# scheme.net
KiCad netlist of a schematic drawn in Altium Designer
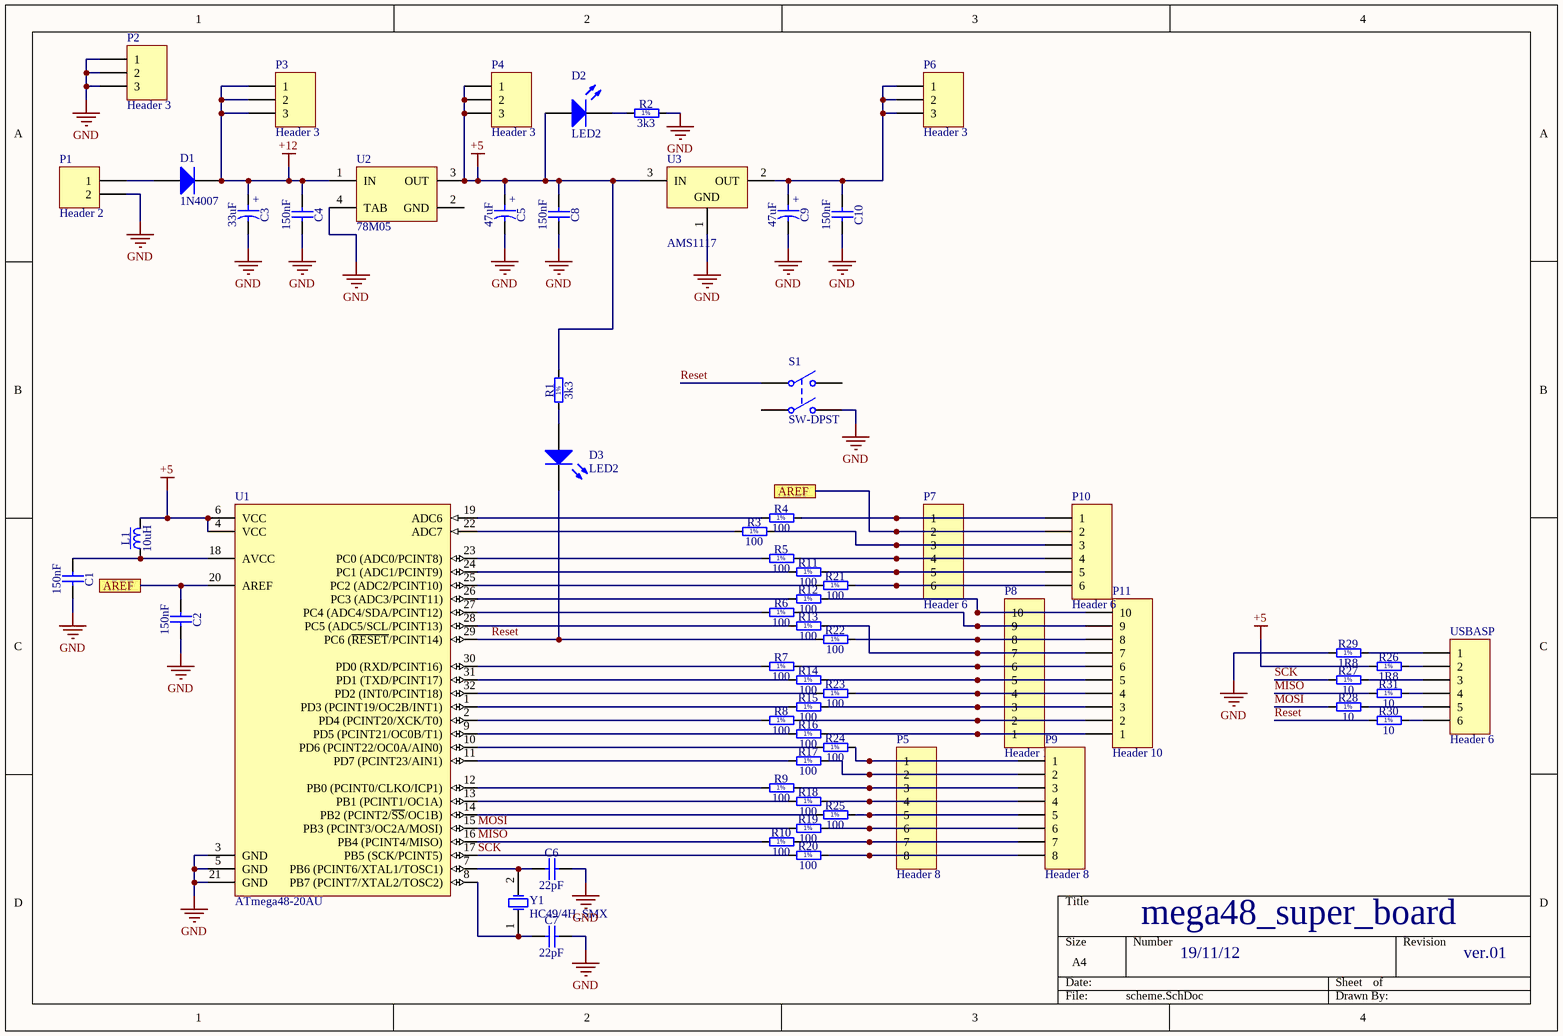
[diagram p0: scheme.SchDoc]

(export (version "E")
  (design (tool "Eeschema 10.0.6"))
  (components
    (comp (ref "C1")
      (value "150nF")
      (footprint "CAPC2013X100N")
      (description "Non-polarised capacitor")
      (fields
        (field (name "PART NUMBER") "CC0805_150NF_50V_10%_X5R")
        (field (name "VOLTAGE") "50V")
        (field (name "AUTHOR") "CERN DEM JLC")
      )
      (libsource (lib "Capacitors") (part "Capacitor - non polarized"))
    )
    (comp (ref "C2")
      (value "150nF")
      (footprint "CAPC2013X100N")
      (description "Non-polarised capacitor")
      (fields
        (field (name "PART NUMBER") "CC0805_150NF_50V_10%_X5R")
        (field (name "VOLTAGE") "50V")
        (field (name "AUTHOR") "CERN DEM JLC")
      )
      (libsource (lib "Capacitors") (part "Capacitor - non polarized"))
    )
    (comp (ref "C3")
      (value "33uF")
      (footprint "CAPMP7343X310N")
      (description "Polarised capacitor")
      (fields
        (field (name "PART NUMBER") "CTE7343-31_33UF_35V_10%_LESR0300")
        (field (name "VOLTAGE") "35V")
        (field (name "AUTHOR") "CERN DEM JLC")
      )
      (libsource (lib "Capacitors") (part "Capacitor - polarized"))
    )
    (comp (ref "C4")
      (value "150nF")
      (footprint "CAPC2013X100N")
      (description "Non-polarised capacitor")
      (fields
        (field (name "PART NUMBER") "CC0805_150NF_50V_10%_X5R")
        (field (name "VOLTAGE") "50V")
        (field (name "AUTHOR") "CERN DEM JLC")
      )
      (libsource (lib "Capacitors") (part "Capacitor - non polarized"))
    )
    (comp (ref "C5")
      (value "47uF")
      (footprint "CAPMP6032X280N")
      (description "Polarised capacitor")
      (fields
        (field (name "PART NUMBER") "CTE6032-28_47UF_10V_10%")
        (field (name "VOLTAGE") "10V")
        (field (name "AUTHOR") "CERN DEM JLC")
      )
      (libsource (lib "Capacitors") (part "Capacitor - polarized"))
    )
    (comp (ref "C6")
      (value "22pF")
      (footprint "CAPC1608X87N")
      (description "Non-polarised capacitor")
      (fields
        (field (name "PART NUMBER") "CC0603_22PF_50V_5%_NP0")
        (field (name "VOLTAGE") "50V")
        (field (name "AUTHOR") "CERN DEM JLC")
      )
      (libsource (lib "Capacitors") (part "Capacitor - non polarized"))
    )
    (comp (ref "C7")
      (value "22pF")
      (footprint "CAPC1608X87N")
      (description "Non-polarised capacitor")
      (fields
        (field (name "PART NUMBER") "CC0603_22PF_50V_5%_NP0")
        (field (name "VOLTAGE") "50V")
        (field (name "AUTHOR") "CERN DEM JLC")
      )
      (libsource (lib "Capacitors") (part "Capacitor - non polarized"))
    )
    (comp (ref "C8")
      (value "150nF")
      (footprint "CAPC2013X100N")
      (description "Non-polarised capacitor")
      (fields
        (field (name "PART NUMBER") "CC0805_150NF_50V_10%_X5R")
        (field (name "VOLTAGE") "50V")
        (field (name "AUTHOR") "CERN DEM JLC")
      )
      (libsource (lib "Capacitors") (part "Capacitor - non polarized"))
    )
    (comp (ref "C9")
      (value "47uF")
      (footprint "CAPMP6032X280N")
      (description "Polarised capacitor")
      (fields
        (field (name "PART NUMBER") "CTE6032-28_47UF_10V_10%")
        (field (name "VOLTAGE") "10V")
        (field (name "AUTHOR") "CERN DEM JLC")
      )
      (libsource (lib "Capacitors") (part "Capacitor - polarized"))
    )
    (comp (ref "C10")
      (value "150nF")
      (footprint "CAPC2013X100N")
      (description "Non-polarised capacitor")
      (fields
        (field (name "PART NUMBER") "CC0805_150NF_50V_10%_X5R")
        (field (name "VOLTAGE") "50V")
        (field (name "AUTHOR") "CERN DEM JLC")
      )
      (libsource (lib "Capacitors") (part "Capacitor - non polarized"))
    )
    (comp (ref "D1")
      (value "1N4007")
      (footprint "DO-41")
      (description "1.0 Ampere General Purpose Rectifier")
      (fields (field (name "PUBLISHER") "Altium Limited"))
      (libsource (lib "FSC Discrete Rectifier") (part "1N4007"))
    )
    (comp (ref "D2")
      (value "LED2")
      (footprint "6-0805_L")
      (description "Typical RED, GREEN, YELLOW, AMBER GaAs LED")
      (fields (field (name "PUBLISHER") "Altium Limited"))
      (libsource (lib "Miscellaneous Devices") (part "LED2"))
    )
    (comp (ref "D3")
      (value "LED2")
      (footprint "6-0805_L")
      (description "Typical RED, GREEN, YELLOW, AMBER GaAs LED")
      (fields (field (name "PUBLISHER") "Altium Limited"))
      (libsource (lib "Miscellaneous Devices") (part "LED2"))
    )
    (comp (ref "L1")
      (value "10uH")
      (footprint "INDC2012X105N")
      (description "Inductor With Core")
      (fields
        (field (name "PART NUMBER") "IND_10UH_10%_MURATA-PS_8200")
        (field (name "POWER") "500mA")
        (field (name "AUTHOR") "CERN DEM JLC")
      )
      (libsource (lib "Inductors & Transformers") (part "Inductor With Magnetic core"))
    )
    (comp (ref "P1")
      (value "Header 2")
      (footprint "HDR1X2")
      (description "Header, 2-Pin")
      (fields (field (name "PUBLISHER") "Altium Limited"))
      (libsource (lib "Miscellaneous Connectors") (part "Header 2"))
    )
    (comp (ref "P2")
      (value "Header 3")
      (footprint "HDR1X3")
      (description "Header, 3-Pin")
      (fields (field (name "PUBLISHER") "Altium Limited"))
      (libsource (lib "Miscellaneous Connectors") (part "Header 3"))
    )
    (comp (ref "P3")
      (value "Header 3")
      (footprint "HDR1X3")
      (description "Header, 3-Pin")
      (fields (field (name "PUBLISHER") "Altium Limited"))
      (libsource (lib "Miscellaneous Connectors") (part "Header 3"))
    )
    (comp (ref "P4")
      (value "Header 3")
      (footprint "HDR1X3")
      (description "Header, 3-Pin")
      (fields (field (name "PUBLISHER") "Altium Limited"))
      (libsource (lib "Miscellaneous Connectors") (part "Header 3"))
    )
    (comp (ref "P5")
      (value "Header 8")
      (footprint "HDR1X8")
      (description "Header, 8-Pin")
      (fields (field (name "PUBLISHER") "Altium Limited"))
      (libsource (lib "Miscellaneous Connectors") (part "Header 8"))
    )
    (comp (ref "P6")
      (value "Header 3")
      (footprint "HDR1X3")
      (description "Header, 3-Pin")
      (fields (field (name "PUBLISHER") "Altium Limited"))
      (libsource (lib "Miscellaneous Connectors") (part "Header 3"))
    )
    (comp (ref "P7")
      (value "Header 6")
      (footprint "HDR1X6")
      (description "Header, 6-Pin")
      (fields (field (name "PUBLISHER") "Altium Limited"))
      (libsource (lib "Miscellaneous Connectors") (part "Header 6"))
    )
    (comp (ref "P8")
      (value "Header 10")
      (footprint "HDR1X10")
      (description "Header, 10-Pin")
      (fields (field (name "PUBLISHER") "Altium Limited"))
      (libsource (lib "Miscellaneous Connectors") (part "Header 10"))
    )
    (comp (ref "P9")
      (value "Header 8")
      (footprint "HDR1X8")
      (description "Header, 8-Pin")
      (fields (field (name "PUBLISHER") "Altium Limited"))
      (libsource (lib "Miscellaneous Connectors") (part "Header 8"))
    )
    (comp (ref "P10")
      (value "Header 6")
      (footprint "HDR1X6")
      (description "Header, 6-Pin")
      (fields (field (name "PUBLISHER") "Altium Limited"))
      (libsource (lib "Miscellaneous Connectors") (part "Header 6"))
    )
    (comp (ref "P11")
      (value "Header 10")
      (footprint "HDR1X10")
      (description "Header, 10-Pin")
      (fields (field (name "PUBLISHER") "Altium Limited"))
      (libsource (lib "Miscellaneous Connectors") (part "Header 10"))
    )
    (comp (ref "R1")
      (value "3k3")
      (footprint "RESC2012X60N")
      (description "Resistor - 1%")
      (fields
        (field (name "PART NUMBER") "R0805_3K3_1%_0.125W_100PPM")
        (field (name "POWER") "0.125W")
        (field (name "AUTHOR") "CERN DEM JLC")
      )
      (libsource (lib "Resistors") (part "Resistor - 1%"))
    )
    (comp (ref "R2")
      (value "3k3")
      (footprint "RESC2012X60N")
      (description "Resistor - 1%")
      (fields
        (field (name "PART NUMBER") "R0805_3K3_1%_0.125W_100PPM")
        (field (name "POWER") "0.125W")
        (field (name "AUTHOR") "CERN DEM JLC")
      )
      (libsource (lib "Resistors") (part "Resistor - 1%"))
    )
    (comp (ref "R3")
      (value "100")
      (footprint "RESC1608X55N")
      (description "Resistor - 1%")
      (fields
        (field (name "PART NUMBER") "R0603_100R_1%_0.1W_100PPM")
        (field (name "POWER") "0.1W")
        (field (name "AUTHOR") "CERN DEM JLC")
      )
      (libsource (lib "Resistors") (part "Resistor - 1%"))
    )
    (comp (ref "R4")
      (value "100")
      (footprint "RESC1608X55N")
      (description "Resistor - 1%")
      (fields
        (field (name "PART NUMBER") "R0603_100R_1%_0.1W_100PPM")
        (field (name "POWER") "0.1W")
        (field (name "AUTHOR") "CERN DEM JLC")
      )
      (libsource (lib "Resistors") (part "Resistor - 1%"))
    )
    (comp (ref "R5")
      (value "100")
      (footprint "RESC1608X55N")
      (description "Resistor - 1%")
      (fields
        (field (name "PART NUMBER") "R0603_100R_1%_0.1W_100PPM")
        (field (name "POWER") "0.1W")
        (field (name "AUTHOR") "CERN DEM JLC")
      )
      (libsource (lib "Resistors") (part "Resistor - 1%"))
    )
    (comp (ref "R6")
      (value "100")
      (footprint "RESC1608X55N")
      (description "Resistor - 1%")
      (fields
        (field (name "PART NUMBER") "R0603_100R_1%_0.1W_100PPM")
        (field (name "POWER") "0.1W")
        (field (name "AUTHOR") "CERN DEM JLC")
      )
      (libsource (lib "Resistors") (part "Resistor - 1%"))
    )
    (comp (ref "R7")
      (value "100")
      (footprint "RESC1608X55N")
      (description "Resistor - 1%")
      (fields
        (field (name "PART NUMBER") "R0603_100R_1%_0.1W_100PPM")
        (field (name "POWER") "0.1W")
        (field (name "AUTHOR") "CERN DEM JLC")
      )
      (libsource (lib "Resistors") (part "Resistor - 1%"))
    )
    (comp (ref "R8")
      (value "100")
      (footprint "RESC1608X55N")
      (description "Resistor - 1%")
      (fields
        (field (name "PART NUMBER") "R0603_100R_1%_0.1W_100PPM")
        (field (name "POWER") "0.1W")
        (field (name "AUTHOR") "CERN DEM JLC")
      )
      (libsource (lib "Resistors") (part "Resistor - 1%"))
    )
    (comp (ref "R9")
      (value "100")
      (footprint "RESC1608X55N")
      (description "Resistor - 1%")
      (fields
        (field (name "PART NUMBER") "R0603_100R_1%_0.1W_100PPM")
        (field (name "POWER") "0.1W")
        (field (name "AUTHOR") "CERN DEM JLC")
      )
      (libsource (lib "Resistors") (part "Resistor - 1%"))
    )
    (comp (ref "R10")
      (value "100")
      (footprint "RESC1608X55N")
      (description "Resistor - 1%")
      (fields
        (field (name "PART NUMBER") "R0603_100R_1%_0.1W_100PPM")
        (field (name "POWER") "0.1W")
        (field (name "AUTHOR") "CERN DEM JLC")
      )
      (libsource (lib "Resistors") (part "Resistor - 1%"))
    )
    (comp (ref "R11")
      (value "100")
      (footprint "RESC1608X55N")
      (description "Resistor - 1%")
      (fields
        (field (name "PART NUMBER") "R0603_100R_1%_0.1W_100PPM")
        (field (name "POWER") "0.1W")
        (field (name "AUTHOR") "CERN DEM JLC")
      )
      (libsource (lib "Resistors") (part "Resistor - 1%"))
    )
    (comp (ref "R12")
      (value "100")
      (footprint "RESC1608X55N")
      (description "Resistor - 1%")
      (fields
        (field (name "PART NUMBER") "R0603_100R_1%_0.1W_100PPM")
        (field (name "POWER") "0.1W")
        (field (name "AUTHOR") "CERN DEM JLC")
      )
      (libsource (lib "Resistors") (part "Resistor - 1%"))
    )
    (comp (ref "R13")
      (value "100")
      (footprint "RESC1608X55N")
      (description "Resistor - 1%")
      (fields
        (field (name "PART NUMBER") "R0603_100R_1%_0.1W_100PPM")
        (field (name "POWER") "0.1W")
        (field (name "AUTHOR") "CERN DEM JLC")
      )
      (libsource (lib "Resistors") (part "Resistor - 1%"))
    )
    (comp (ref "R14")
      (value "100")
      (footprint "RESC1608X55N")
      (description "Resistor - 1%")
      (fields
        (field (name "PART NUMBER") "R0603_100R_1%_0.1W_100PPM")
        (field (name "POWER") "0.1W")
        (field (name "AUTHOR") "CERN DEM JLC")
      )
      (libsource (lib "Resistors") (part "Resistor - 1%"))
    )
    (comp (ref "R15")
      (value "100")
      (footprint "RESC1608X55N")
      (description "Resistor - 1%")
      (fields
        (field (name "PART NUMBER") "R0603_100R_1%_0.1W_100PPM")
        (field (name "POWER") "0.1W")
        (field (name "AUTHOR") "CERN DEM JLC")
      )
      (libsource (lib "Resistors") (part "Resistor - 1%"))
    )
    (comp (ref "R16")
      (value "100")
      (footprint "RESC1608X55N")
      (description "Resistor - 1%")
      (fields
        (field (name "PART NUMBER") "R0603_100R_1%_0.1W_100PPM")
        (field (name "POWER") "0.1W")
        (field (name "AUTHOR") "CERN DEM JLC")
      )
      (libsource (lib "Resistors") (part "Resistor - 1%"))
    )
    (comp (ref "R17")
      (value "100")
      (footprint "RESC1608X55N")
      (description "Resistor - 1%")
      (fields
        (field (name "PART NUMBER") "R0603_100R_1%_0.1W_100PPM")
        (field (name "POWER") "0.1W")
        (field (name "AUTHOR") "CERN DEM JLC")
      )
      (libsource (lib "Resistors") (part "Resistor - 1%"))
    )
    (comp (ref "R18")
      (value "100")
      (footprint "RESC1608X55N")
      (description "Resistor - 1%")
      (fields
        (field (name "PART NUMBER") "R0603_100R_1%_0.1W_100PPM")
        (field (name "POWER") "0.1W")
        (field (name "AUTHOR") "CERN DEM JLC")
      )
      (libsource (lib "Resistors") (part "Resistor - 1%"))
    )
    (comp (ref "R19")
      (value "100")
      (footprint "RESC1608X55N")
      (description "Resistor - 1%")
      (fields
        (field (name "PART NUMBER") "R0603_100R_1%_0.1W_100PPM")
        (field (name "POWER") "0.1W")
        (field (name "AUTHOR") "CERN DEM JLC")
      )
      (libsource (lib "Resistors") (part "Resistor - 1%"))
    )
    (comp (ref "R20")
      (value "100")
      (footprint "RESC1608X55N")
      (description "Resistor - 1%")
      (fields
        (field (name "PART NUMBER") "R0603_100R_1%_0.1W_100PPM")
        (field (name "POWER") "0.1W")
        (field (name "AUTHOR") "CERN DEM JLC")
      )
      (libsource (lib "Resistors") (part "Resistor - 1%"))
    )
    (comp (ref "R21")
      (value "100")
      (footprint "RESC1608X55N")
      (description "Resistor - 1%")
      (fields
        (field (name "PART NUMBER") "R0603_100R_1%_0.1W_100PPM")
        (field (name "POWER") "0.1W")
        (field (name "AUTHOR") "CERN DEM JLC")
      )
      (libsource (lib "Resistors") (part "Resistor - 1%"))
    )
    (comp (ref "R22")
      (value "100")
      (footprint "RESC1608X55N")
      (description "Resistor - 1%")
      (fields
        (field (name "PART NUMBER") "R0603_100R_1%_0.1W_100PPM")
        (field (name "POWER") "0.1W")
        (field (name "AUTHOR") "CERN DEM JLC")
      )
      (libsource (lib "Resistors") (part "Resistor - 1%"))
    )
    (comp (ref "R23")
      (value "100")
      (footprint "RESC1608X55N")
      (description "Resistor - 1%")
      (fields
        (field (name "PART NUMBER") "R0603_100R_1%_0.1W_100PPM")
        (field (name "POWER") "0.1W")
        (field (name "AUTHOR") "CERN DEM JLC")
      )
      (libsource (lib "Resistors") (part "Resistor - 1%"))
    )
    (comp (ref "R24")
      (value "100")
      (footprint "RESC1608X55N")
      (description "Resistor - 1%")
      (fields
        (field (name "PART NUMBER") "R0603_100R_1%_0.1W_100PPM")
        (field (name "POWER") "0.1W")
        (field (name "AUTHOR") "CERN DEM JLC")
      )
      (libsource (lib "Resistors") (part "Resistor - 1%"))
    )
    (comp (ref "R25")
      (value "100")
      (footprint "RESC1608X55N")
      (description "Resistor - 1%")
      (fields
        (field (name "PART NUMBER") "R0603_100R_1%_0.1W_100PPM")
        (field (name "POWER") "0.1W")
        (field (name "AUTHOR") "CERN DEM JLC")
      )
      (libsource (lib "Resistors") (part "Resistor - 1%"))
    )
    (comp (ref "R26")
      (value "1R8")
      (footprint "RESC1608X55N")
      (description "Resistor - 1%")
      (fields
        (field (name "PART NUMBER") "R0603_1R8_1%_0.1W_200PPM")
        (field (name "POWER") "0.1W")
        (field (name "AUTHOR") "CERN DEM JLC")
      )
      (libsource (lib "Resistors") (part "Resistor - 1%"))
    )
    (comp (ref "R27")
      (value "10")
      (footprint "RESC1608X55N")
      (description "Resistor - 1%")
      (fields
        (field (name "PART NUMBER") "R0603_10R_1%_0.1W_200PPM")
        (field (name "POWER") "0.1W")
        (field (name "AUTHOR") "CERN DEM JLC")
      )
      (libsource (lib "Resistors") (part "Resistor - 1%"))
    )
    (comp (ref "R28")
      (value "10")
      (footprint "RESC1608X55N")
      (description "Resistor - 1%")
      (fields
        (field (name "PART NUMBER") "R0603_10R_1%_0.1W_200PPM")
        (field (name "POWER") "0.1W")
        (field (name "AUTHOR") "CERN DEM JLC")
      )
      (libsource (lib "Resistors") (part "Resistor - 1%"))
    )
    (comp (ref "R29")
      (value "1R8")
      (footprint "RESC1608X55N")
      (description "Resistor - 1%")
      (fields
        (field (name "PART NUMBER") "R0603_1R8_1%_0.1W_200PPM")
        (field (name "POWER") "0.1W")
        (field (name "AUTHOR") "CERN DEM JLC")
      )
      (libsource (lib "Resistors") (part "Resistor - 1%"))
    )
    (comp (ref "R30")
      (value "10")
      (footprint "RESC1608X55N")
      (description "Resistor - 1%")
      (fields
        (field (name "PART NUMBER") "R0603_10R_1%_0.1W_200PPM")
        (field (name "POWER") "0.1W")
        (field (name "AUTHOR") "CERN DEM JLC")
      )
      (libsource (lib "Resistors") (part "Resistor - 1%"))
    )
    (comp (ref "R31")
      (value "10")
      (footprint "RESC1608X55N")
      (description "Resistor - 1%")
      (fields
        (field (name "PART NUMBER") "R0603_10R_1%_0.1W_200PPM")
        (field (name "POWER") "0.1W")
        (field (name "AUTHOR") "CERN DEM JLC")
      )
      (libsource (lib "Resistors") (part "Resistor - 1%"))
    )
    (comp (ref "S1")
      (value "SW-DPST")
      (footprint "DPST-4")
      (description "Double-Pole, Single-Throw Switch")
      (fields (field (name "PUBLISHER") "Altium Limited"))
      (libsource (lib "Miscellaneous Devices") (part "SW-DPST"))
    )
    (comp (ref "U1")
      (value "ATmega48-20AU")
      (footprint "32A_N")
      (libsource (lib "Atmel Microcontroller megaAVR") (part "ATmega48-20AU"))
    )
    (comp (ref "U2")
      (value "78M05")
      (footprint "TS3B_N")
      (description "Series 3-Terminal Positive Regulators, 3-pin TO-263")
      (fields (field (name "PARTNUMBER") "LM340S-5.0") (field (name "MANUFACTURER") "National Semiconductor"))
      (libsource (lib "National Semiconductor LDO") (part "LM340S-5.0"))
    )
    (comp (ref "U3")
      (value "AMS1117")
      (footprint "ADI-KC-3_N")
      (fields (field (name "MANUFACTURER") "Analog Devices") (field (name "PARTNUMBER") "ADP3338AKCZ-3.3-RL"))
      (libsource (lib "Analog Devices Power Management Linear Regulators") (part "ADP3338AKCZ-3.3-RL"))
    )
    (comp (ref "USBASP")
      (value "Header 6")
      (footprint "HDR1X6")
      (description "Header, 6-Pin")
      (fields (field (name "PUBLISHER") "Altium Limited"))
      (libsource (lib "Miscellaneous Connectors") (part "Header 6"))
    )
    (comp (ref "Y1")
      (value "HC49/4H_SMX")
      (footprint "HC49/4H_SMX")
      (description "Surface Mount Quartz Crystal")
      (fields (field (name "PUBLISHER") "Altium Limited"))
      (libsource (lib "C-MAC Crystal Oscillator") (part "HC49/4H_SMX"))
    )
  )
  (nets
    (net (code "1") (name "+5") (class "Default")
      (node (ref "C5") (pin "1") (pinfunction "1_1") (pintype "passive"))
      (node (ref "C8") (pin "1") (pinfunction "1_1") (pintype "passive"))
      (node (ref "D2") (pin "1") (pinfunction "A_1") (pintype "passive"))
      (node (ref "L1") (pin "2") (pinfunction "2_2") (pintype "passive"))
      (node (ref "P4") (pin "1") (pinfunction "1_1") (pintype "passive"))
      (node (ref "P4") (pin "2") (pinfunction "2_2") (pintype "passive"))
      (node (ref "P4") (pin "3") (pinfunction "3_3") (pintype "passive"))
      (node (ref "R1") (pin "2") (pinfunction "2_2") (pintype "passive"))
      (node (ref "R26") (pin "1") (pinfunction "1_1") (pintype "passive"))
      (node (ref "U1") (pin "4") (pinfunction "VCC_4") (pintype "power_in"))
      (node (ref "U1") (pin "6") (pinfunction "VCC_6") (pintype "power_in"))
      (node (ref "U2") (pin "3") (pinfunction "OUT_3") (pintype "power_in"))
      (node (ref "U3") (pin "3") (pinfunction "IN_3") (pintype "power_in"))
    )
    (net (code "2") (name "+12") (class "Default")
      (node (ref "C3") (pin "1") (pinfunction "1_1") (pintype "passive"))
      (node (ref "C4") (pin "1") (pinfunction "1_1") (pintype "passive"))
      (node (ref "D1") (pin "2") (pinfunction "K_2") (pintype "passive"))
      (node (ref "P3") (pin "1") (pinfunction "1_1") (pintype "passive"))
      (node (ref "P3") (pin "2") (pinfunction "2_2") (pintype "passive"))
      (node (ref "P3") (pin "3") (pinfunction "3_3") (pintype "passive"))
      (node (ref "U2") (pin "1") (pinfunction "IN_1") (pintype "power_in"))
    )
    (net (code "3") (name "/AREF") (class "Default")
      (node (ref "C2") (pin "1") (pinfunction "1_1") (pintype "passive"))
      (node (ref "P10") (pin "2") (pinfunction "2_2") (pintype "passive"))
      (node (ref "P7") (pin "2") (pinfunction "2_2") (pintype "passive"))
      (node (ref "U1") (pin "20") (pinfunction "AREF_20") (pintype "passive"))
    )
    (net (code "4") (name "/MISO") (class "Default")
      (node (ref "R10") (pin "1") (pinfunction "1_1") (pintype "passive"))
      (node (ref "R31") (pin "1") (pinfunction "1_1") (pintype "passive"))
      (node (ref "U1") (pin "16") (pinfunction "PB4_(PCINT4/MISO)_16") (pintype "bidirectional"))
    )
    (net (code "5") (name "/MOSI") (class "Default")
      (node (ref "R19") (pin "1") (pinfunction "1_1") (pintype "passive"))
      (node (ref "R28") (pin "1") (pinfunction "1_1") (pintype "passive"))
      (node (ref "U1") (pin "15") (pinfunction "PB3_(PCINT3/OC2A/MOSI)_15") (pintype "bidirectional"))
    )
    (net (code "6") (name "/Reset") (class "Default")
      (node (ref "D3") (pin "2") (pinfunction "K_2") (pintype "passive"))
      (node (ref "R22") (pin "1") (pinfunction "1_1") (pintype "passive"))
      (node (ref "R30") (pin "1") (pinfunction "1_1") (pintype "passive"))
      (node (ref "S1") (pin "1") (pinfunction "COMMON1_1") (pintype "passive"))
      (node (ref "U1") (pin "29") (pinfunction "PC6_(~{RESET}/PCINT14)_29") (pintype "bidirectional"))
    )
    (net (code "7") (name "/SCK") (class "Default")
      (node (ref "R20") (pin "1") (pinfunction "1_1") (pintype "passive"))
      (node (ref "R27") (pin "1") (pinfunction "1_1") (pintype "passive"))
      (node (ref "U1") (pin "17") (pinfunction "PB5_(SCK/PCINT5)_17") (pintype "bidirectional"))
    )
    (net (code "8") (name "GND") (class "Default")
      (node (ref "C1") (pin "2") (pinfunction "2_2") (pintype "passive"))
      (node (ref "C10") (pin "2") (pinfunction "2_2") (pintype "passive"))
      (node (ref "C2") (pin "2") (pinfunction "2_2") (pintype "passive"))
      (node (ref "C3") (pin "2") (pinfunction "2_2") (pintype "passive"))
      (node (ref "C4") (pin "2") (pinfunction "2_2") (pintype "passive"))
      (node (ref "C5") (pin "2") (pinfunction "2_2") (pintype "passive"))
      (node (ref "C6") (pin "2") (pinfunction "2_2") (pintype "passive"))
      (node (ref "C7") (pin "2") (pinfunction "2_2") (pintype "passive"))
      (node (ref "C8") (pin "2") (pinfunction "2_2") (pintype "passive"))
      (node (ref "C9") (pin "2") (pinfunction "2_2") (pintype "passive"))
      (node (ref "P1") (pin "2") (pinfunction "2_2") (pintype "passive"))
      (node (ref "P2") (pin "1") (pinfunction "1_1") (pintype "passive"))
      (node (ref "P2") (pin "2") (pinfunction "2_2") (pintype "passive"))
      (node (ref "P2") (pin "3") (pinfunction "3_3") (pintype "passive"))
      (node (ref "R2") (pin "2") (pinfunction "2_2") (pintype "passive"))
      (node (ref "R29") (pin "1") (pinfunction "1_1") (pintype "passive"))
      (node (ref "S1") (pin "4") (pinfunction "NO2_4") (pintype "passive"))
      (node (ref "U1") (pin "21") (pinfunction "GND_21") (pintype "power_in"))
      (node (ref "U1") (pin "3") (pinfunction "GND_3") (pintype "power_in"))
      (node (ref "U1") (pin "5") (pinfunction "GND_5") (pintype "power_in"))
      (node (ref "U2") (pin "4") (pinfunction "TAB_4") (pintype "power_in"))
      (node (ref "U3") (pin "1") (pinfunction "GND_1") (pintype "power_in"))
    )
    (net (code "9") (name "Net-(D1-A)") (class "Default")
      (node (ref "D1") (pin "1") (pinfunction "A_1") (pintype "passive"))
      (node (ref "P1") (pin "1") (pinfunction "1_1") (pintype "passive"))
    )
    (net (code "10") (name "Net-(D2-K)") (class "Default")
      (node (ref "D2") (pin "2") (pinfunction "K_2") (pintype "passive"))
      (node (ref "R2") (pin "1") (pinfunction "1_1") (pintype "passive"))
    )
    (net (code "11") (name "Net-(D3-A)") (class "Default")
      (node (ref "D3") (pin "1") (pinfunction "A_1") (pintype "passive"))
      (node (ref "R1") (pin "1") (pinfunction "1_1") (pintype "passive"))
    )
    (net (code "12") (name "Net-(P5-Pad1)") (class "Default")
      (node (ref "P5") (pin "1") (pinfunction "1_1") (pintype "passive"))
      (node (ref "P9") (pin "1") (pinfunction "1_1") (pintype "passive"))
      (node (ref "R24") (pin "2") (pinfunction "2_2") (pintype "passive"))
    )
    (net (code "13") (name "Net-(P5-Pad2)") (class "Default")
      (node (ref "P5") (pin "2") (pinfunction "2_2") (pintype "passive"))
      (node (ref "P9") (pin "2") (pinfunction "2_2") (pintype "passive"))
      (node (ref "R17") (pin "2") (pinfunction "2_2") (pintype "passive"))
    )
    (net (code "14") (name "Net-(P5-Pad3)") (class "Default")
      (node (ref "P5") (pin "3") (pinfunction "3_3") (pintype "passive"))
      (node (ref "P9") (pin "3") (pinfunction "3_3") (pintype "passive"))
      (node (ref "R9") (pin "2") (pinfunction "2_2") (pintype "passive"))
    )
    (net (code "15") (name "Net-(P5-Pad4)") (class "Default")
      (node (ref "P5") (pin "4") (pinfunction "4_4") (pintype "passive"))
      (node (ref "P9") (pin "4") (pinfunction "4_4") (pintype "passive"))
      (node (ref "R18") (pin "2") (pinfunction "2_2") (pintype "passive"))
    )
    (net (code "16") (name "Net-(P5-Pad5)") (class "Default")
      (node (ref "P5") (pin "5") (pinfunction "5_5") (pintype "passive"))
      (node (ref "P9") (pin "5") (pinfunction "5_5") (pintype "passive"))
      (node (ref "R25") (pin "2") (pinfunction "2_2") (pintype "passive"))
    )
    (net (code "17") (name "Net-(P5-Pad6)") (class "Default")
      (node (ref "P5") (pin "6") (pinfunction "6_6") (pintype "passive"))
      (node (ref "P9") (pin "6") (pinfunction "6_6") (pintype "passive"))
      (node (ref "R19") (pin "2") (pinfunction "2_2") (pintype "passive"))
    )
    (net (code "18") (name "Net-(P5-Pad7)") (class "Default")
      (node (ref "P5") (pin "7") (pinfunction "7_7") (pintype "passive"))
      (node (ref "P9") (pin "7") (pinfunction "7_7") (pintype "passive"))
      (node (ref "R10") (pin "2") (pinfunction "2_2") (pintype "passive"))
    )
    (net (code "19") (name "Net-(P5-Pad8)") (class "Default")
      (node (ref "P5") (pin "8") (pinfunction "8_8") (pintype "passive"))
      (node (ref "P9") (pin "8") (pinfunction "8_8") (pintype "passive"))
      (node (ref "R20") (pin "2") (pinfunction "2_2") (pintype "passive"))
    )
    (net (code "20") (name "Net-(P10-Pad1)") (class "Default")
      (node (ref "P10") (pin "1") (pinfunction "1_1") (pintype "passive"))
      (node (ref "P7") (pin "1") (pinfunction "1_1") (pintype "passive"))
      (node (ref "R4") (pin "2") (pinfunction "2_2") (pintype "passive"))
    )
    (net (code "21") (name "Net-(P10-Pad3)") (class "Default")
      (node (ref "P10") (pin "3") (pinfunction "3_3") (pintype "passive"))
      (node (ref "P7") (pin "3") (pinfunction "3_3") (pintype "passive"))
      (node (ref "R3") (pin "2") (pinfunction "2_2") (pintype "passive"))
    )
    (net (code "22") (name "Net-(P10-Pad4)") (class "Default")
      (node (ref "P10") (pin "4") (pinfunction "4_4") (pintype "passive"))
      (node (ref "P7") (pin "4") (pinfunction "4_4") (pintype "passive"))
      (node (ref "R5") (pin "2") (pinfunction "2_2") (pintype "passive"))
    )
    (net (code "23") (name "Net-(P10-Pad5)") (class "Default")
      (node (ref "P10") (pin "5") (pinfunction "5_5") (pintype "passive"))
      (node (ref "P7") (pin "5") (pinfunction "5_5") (pintype "passive"))
      (node (ref "R11") (pin "2") (pinfunction "2_2") (pintype "passive"))
    )
    (net (code "24") (name "Net-(P10-Pad6)") (class "Default")
      (node (ref "P10") (pin "6") (pinfunction "6_6") (pintype "passive"))
      (node (ref "P7") (pin "6") (pinfunction "6_6") (pintype "passive"))
      (node (ref "R21") (pin "2") (pinfunction "2_2") (pintype "passive"))
    )
    (net (code "25") (name "Net-(P11-Pad1)") (class "Default")
      (node (ref "P11") (pin "1") (pinfunction "1_1") (pintype "passive"))
      (node (ref "P8") (pin "1") (pinfunction "1_1") (pintype "passive"))
      (node (ref "R16") (pin "2") (pinfunction "2_2") (pintype "passive"))
    )
    (net (code "26") (name "Net-(P11-Pad2)") (class "Default")
      (node (ref "P11") (pin "2") (pinfunction "2_2") (pintype "passive"))
      (node (ref "P8") (pin "2") (pinfunction "2_2") (pintype "passive"))
      (node (ref "R8") (pin "2") (pinfunction "2_2") (pintype "passive"))
    )
    (net (code "27") (name "Net-(P11-Pad3)") (class "Default")
      (node (ref "P11") (pin "3") (pinfunction "3_3") (pintype "passive"))
      (node (ref "P8") (pin "3") (pinfunction "3_3") (pintype "passive"))
      (node (ref "R15") (pin "2") (pinfunction "2_2") (pintype "passive"))
    )
    (net (code "28") (name "Net-(P11-Pad4)") (class "Default")
      (node (ref "P11") (pin "4") (pinfunction "4_4") (pintype "passive"))
      (node (ref "P8") (pin "4") (pinfunction "4_4") (pintype "passive"))
      (node (ref "R23") (pin "2") (pinfunction "2_2") (pintype "passive"))
    )
    (net (code "29") (name "Net-(P11-Pad5)") (class "Default")
      (node (ref "P11") (pin "5") (pinfunction "5_5") (pintype "passive"))
      (node (ref "P8") (pin "5") (pinfunction "5_5") (pintype "passive"))
      (node (ref "R14") (pin "2") (pinfunction "2_2") (pintype "passive"))
    )
    (net (code "30") (name "Net-(P11-Pad6)") (class "Default")
      (node (ref "P11") (pin "6") (pinfunction "6_6") (pintype "passive"))
      (node (ref "P8") (pin "6") (pinfunction "6_6") (pintype "passive"))
      (node (ref "R7") (pin "2") (pinfunction "2_2") (pintype "passive"))
    )
    (net (code "31") (name "Net-(P11-Pad7)") (class "Default")
      (node (ref "P11") (pin "7") (pinfunction "7_7") (pintype "passive"))
      (node (ref "P8") (pin "7") (pinfunction "7_7") (pintype "passive"))
      (node (ref "R13") (pin "2") (pinfunction "2_2") (pintype "passive"))
    )
    (net (code "32") (name "Net-(P11-Pad8)") (class "Default")
      (node (ref "P11") (pin "8") (pinfunction "8_8") (pintype "passive"))
      (node (ref "P8") (pin "8") (pinfunction "8_8") (pintype "passive"))
      (node (ref "R22") (pin "2") (pinfunction "2_2") (pintype "passive"))
    )
    (net (code "33") (name "Net-(P11-Pad9)") (class "Default")
      (node (ref "P11") (pin "9") (pinfunction "9_9") (pintype "passive"))
      (node (ref "P8") (pin "9") (pinfunction "9_9") (pintype "passive"))
      (node (ref "R6") (pin "2") (pinfunction "2_2") (pintype "passive"))
    )
    (net (code "34") (name "Net-(P11-Pad10)") (class "Default")
      (node (ref "P11") (pin "10") (pinfunction "10_10") (pintype "passive"))
      (node (ref "P8") (pin "10") (pinfunction "10_10") (pintype "passive"))
      (node (ref "R12") (pin "2") (pinfunction "2_2") (pintype "passive"))
    )
    (net (code "35") (name "Net-(R26-Pad2)") (class "Default")
      (node (ref "R26") (pin "2") (pinfunction "2_2") (pintype "passive"))
      (node (ref "USBASP") (pin "2") (pinfunction "2_2") (pintype "passive"))
    )
    (net (code "36") (name "Net-(R27-Pad2)") (class "Default")
      (node (ref "R27") (pin "2") (pinfunction "2_2") (pintype "passive"))
      (node (ref "USBASP") (pin "3") (pinfunction "3_3") (pintype "passive"))
    )
    (net (code "37") (name "Net-(R28-Pad2)") (class "Default")
      (node (ref "R28") (pin "2") (pinfunction "2_2") (pintype "passive"))
      (node (ref "USBASP") (pin "5") (pinfunction "5_5") (pintype "passive"))
    )
    (net (code "38") (name "Net-(R29-Pad2)") (class "Default")
      (node (ref "R29") (pin "2") (pinfunction "2_2") (pintype "passive"))
      (node (ref "USBASP") (pin "1") (pinfunction "1_1") (pintype "passive"))
    )
    (net (code "39") (name "Net-(R30-Pad2)") (class "Default")
      (node (ref "R30") (pin "2") (pinfunction "2_2") (pintype "passive"))
      (node (ref "USBASP") (pin "6") (pinfunction "6_6") (pintype "passive"))
    )
    (net (code "40") (name "Net-(R31-Pad2)") (class "Default")
      (node (ref "R31") (pin "2") (pinfunction "2_2") (pintype "passive"))
      (node (ref "USBASP") (pin "4") (pinfunction "4_4") (pintype "passive"))
    )
    (net (code "41") (name "Net-(U1-ADC6)") (class "Default")
      (node (ref "R4") (pin "1") (pinfunction "1_1") (pintype "passive"))
      (node (ref "U1") (pin "19") (pinfunction "ADC6_19") (pintype "input"))
    )
    (net (code "42") (name "Net-(U1-ADC7)") (class "Default")
      (node (ref "R3") (pin "1") (pinfunction "1_1") (pintype "passive"))
      (node (ref "U1") (pin "22") (pinfunction "ADC7_22") (pintype "input"))
    )
    (net (code "43") (name "Net-(U1-AVCC)") (class "Default")
      (node (ref "C1") (pin "1") (pinfunction "1_1") (pintype "passive"))
      (node (ref "L1") (pin "1") (pinfunction "1_1") (pintype "passive"))
      (node (ref "U1") (pin "18") (pinfunction "AVCC_18") (pintype "power_in"))
    )
    (net (code "44") (name "Net-(U1-PB0_(PCINT0{slash}CLKO{slash}ICP1))") (class "Default")
      (node (ref "R9") (pin "1") (pinfunction "1_1") (pintype "passive"))
      (node (ref "U1") (pin "12") (pinfunction "PB0_(PCINT0/CLKO/ICP1)_12") (pintype "bidirectional"))
    )
    (net (code "45") (name "Net-(U1-PB1_(PCINT1{slash}OC1A))") (class "Default")
      (node (ref "R18") (pin "1") (pinfunction "1_1") (pintype "passive"))
      (node (ref "U1") (pin "13") (pinfunction "PB1_(PCINT1/OC1A)_13") (pintype "bidirectional"))
    )
    (net (code "46") (name "Net-(U1-PB2_(PCINT2{slash}~{SS}{slash}OC1B))") (class "Default")
      (node (ref "R25") (pin "1") (pinfunction "1_1") (pintype "passive"))
      (node (ref "U1") (pin "14") (pinfunction "PB2_(PCINT2/~{SS}/OC1B)_14") (pintype "bidirectional"))
    )
    (net (code "47") (name "Net-(U1-PB6_(PCINT6{slash}XTAL1{slash}TOSC1))") (class "Default")
      (node (ref "C6") (pin "1") (pinfunction "1_1") (pintype "passive"))
      (node (ref "U1") (pin "7") (pinfunction "PB6_(PCINT6/XTAL1/TOSC1)_7") (pintype "bidirectional"))
      (node (ref "Y1") (pin "2") (pinfunction "OSC2_2") (pintype "passive"))
    )
    (net (code "48") (name "Net-(U1-PB7_(PCINT7{slash}XTAL2{slash}TOSC2))") (class "Default")
      (node (ref "C7") (pin "1") (pinfunction "1_1") (pintype "passive"))
      (node (ref "U1") (pin "8") (pinfunction "PB7_(PCINT7/XTAL2/TOSC2)_8") (pintype "bidirectional"))
      (node (ref "Y1") (pin "1") (pinfunction "OSC1_1") (pintype "passive"))
    )
    (net (code "49") (name "Net-(U1-PC0_(ADC0{slash}PCINT8))") (class "Default")
      (node (ref "R5") (pin "1") (pinfunction "1_1") (pintype "passive"))
      (node (ref "U1") (pin "23") (pinfunction "PC0_(ADC0/PCINT8)_23") (pintype "bidirectional"))
    )
    (net (code "50") (name "Net-(U1-PC1_(ADC1{slash}PCINT9))") (class "Default")
      (node (ref "R11") (pin "1") (pinfunction "1_1") (pintype "passive"))
      (node (ref "U1") (pin "24") (pinfunction "PC1_(ADC1/PCINT9)_24") (pintype "bidirectional"))
    )
    (net (code "51") (name "Net-(U1-PC2_(ADC2{slash}PCINT10))") (class "Default")
      (node (ref "R21") (pin "1") (pinfunction "1_1") (pintype "passive"))
      (node (ref "U1") (pin "25") (pinfunction "PC2_(ADC2/PCINT10)_25") (pintype "bidirectional"))
    )
    (net (code "52") (name "Net-(U1-PC3_(ADC3{slash}PCINT11))") (class "Default")
      (node (ref "R12") (pin "1") (pinfunction "1_1") (pintype "passive"))
      (node (ref "U1") (pin "26") (pinfunction "PC3_(ADC3/PCINT11)_26") (pintype "bidirectional"))
    )
    (net (code "53") (name "Net-(U1-PC4_(ADC4{slash}SDA{slash}PCINT12))") (class "Default")
      (node (ref "R6") (pin "1") (pinfunction "1_1") (pintype "passive"))
      (node (ref "U1") (pin "27") (pinfunction "PC4_(ADC4/SDA/PCINT12)_27") (pintype "bidirectional"))
    )
    (net (code "54") (name "Net-(U1-PC5_(ADC5{slash}SCL{slash}PCINT13))") (class "Default")
      (node (ref "R13") (pin "1") (pinfunction "1_1") (pintype "passive"))
      (node (ref "U1") (pin "28") (pinfunction "PC5_(ADC5/SCL/PCINT13)_28") (pintype "bidirectional"))
    )
    (net (code "55") (name "Net-(U1-PD0_(RXD{slash}PCINT16))") (class "Default")
      (node (ref "R7") (pin "1") (pinfunction "1_1") (pintype "passive"))
      (node (ref "U1") (pin "30") (pinfunction "PD0_(RXD/PCINT16)_30") (pintype "bidirectional"))
    )
    (net (code "56") (name "Net-(U1-PD1_(TXD{slash}PCINT17))") (class "Default")
      (node (ref "R14") (pin "1") (pinfunction "1_1") (pintype "passive"))
      (node (ref "U1") (pin "31") (pinfunction "PD1_(TXD/PCINT17)_31") (pintype "bidirectional"))
    )
    (net (code "57") (name "Net-(U1-PD2_(INT0{slash}PCINT18))") (class "Default")
      (node (ref "R23") (pin "1") (pinfunction "1_1") (pintype "passive"))
      (node (ref "U1") (pin "32") (pinfunction "PD2_(INT0/PCINT18)_32") (pintype "bidirectional"))
    )
    (net (code "58") (name "Net-(U1-PD3_(PCINT19{slash}OC2B{slash}INT1))") (class "Default")
      (node (ref "R15") (pin "1") (pinfunction "1_1") (pintype "passive"))
      (node (ref "U1") (pin "1") (pinfunction "PD3_(PCINT19/OC2B/INT1)_1") (pintype "bidirectional"))
    )
    (net (code "59") (name "Net-(U1-PD4_(PCINT20{slash}XCK{slash}T0))") (class "Default")
      (node (ref "R8") (pin "1") (pinfunction "1_1") (pintype "passive"))
      (node (ref "U1") (pin "2") (pinfunction "PD4_(PCINT20/XCK/T0)_2") (pintype "bidirectional"))
    )
    (net (code "60") (name "Net-(U1-PD5_(PCINT21{slash}OC0B{slash}T1))") (class "Default")
      (node (ref "R16") (pin "1") (pinfunction "1_1") (pintype "passive"))
      (node (ref "U1") (pin "9") (pinfunction "PD5_(PCINT21/OC0B/T1)_9") (pintype "bidirectional"))
    )
    (net (code "61") (name "Net-(U1-PD6_(PCINT22{slash}OC0A{slash}AIN0))") (class "Default")
      (node (ref "R24") (pin "1") (pinfunction "1_1") (pintype "passive"))
      (node (ref "U1") (pin "10") (pinfunction "PD6_(PCINT22/OC0A/AIN0)_10") (pintype "bidirectional"))
    )
    (net (code "62") (name "Net-(U1-PD7_(PCINT23{slash}AIN1))") (class "Default")
      (node (ref "R17") (pin "1") (pinfunction "1_1") (pintype "passive"))
      (node (ref "U1") (pin "11") (pinfunction "PD7_(PCINT23/AIN1)_11") (pintype "bidirectional"))
    )
    (net (code "63") (name "Net-(U3-OUT)") (class "Default")
      (node (ref "C10") (pin "1") (pinfunction "1_1") (pintype "passive"))
      (node (ref "C9") (pin "1") (pinfunction "1_1") (pintype "passive"))
      (node (ref "P6") (pin "1") (pinfunction "1_1") (pintype "passive"))
      (node (ref "P6") (pin "2") (pinfunction "2_2") (pintype "passive"))
      (node (ref "P6") (pin "3") (pinfunction "3_3") (pintype "passive"))
      (node (ref "U3") (pin "2") (pinfunction "OUT_2") (pintype "power_in"))
    )
    (net (code "64") (name "unconnected-(S1-COMMON2-Pad3)") (class "Default")
      (node (ref "S1") (pin "3") (pinfunction "COMMON2_3") (pintype "passive"))
    )
    (net (code "65") (name "unconnected-(S1-NO1-Pad2)") (class "Default")
      (node (ref "S1") (pin "2") (pinfunction "NO1_2") (pintype "passive"))
    )
    (net (code "66") (name "unconnected-(U2-GND-Pad2)") (class "Default")
      (node (ref "U2") (pin "2") (pinfunction "GND_2") (pintype "power_in"))
    )
  )
)
